# PWR_MGMT.net
KiCad netlist of a schematic drawn in Altium Designer
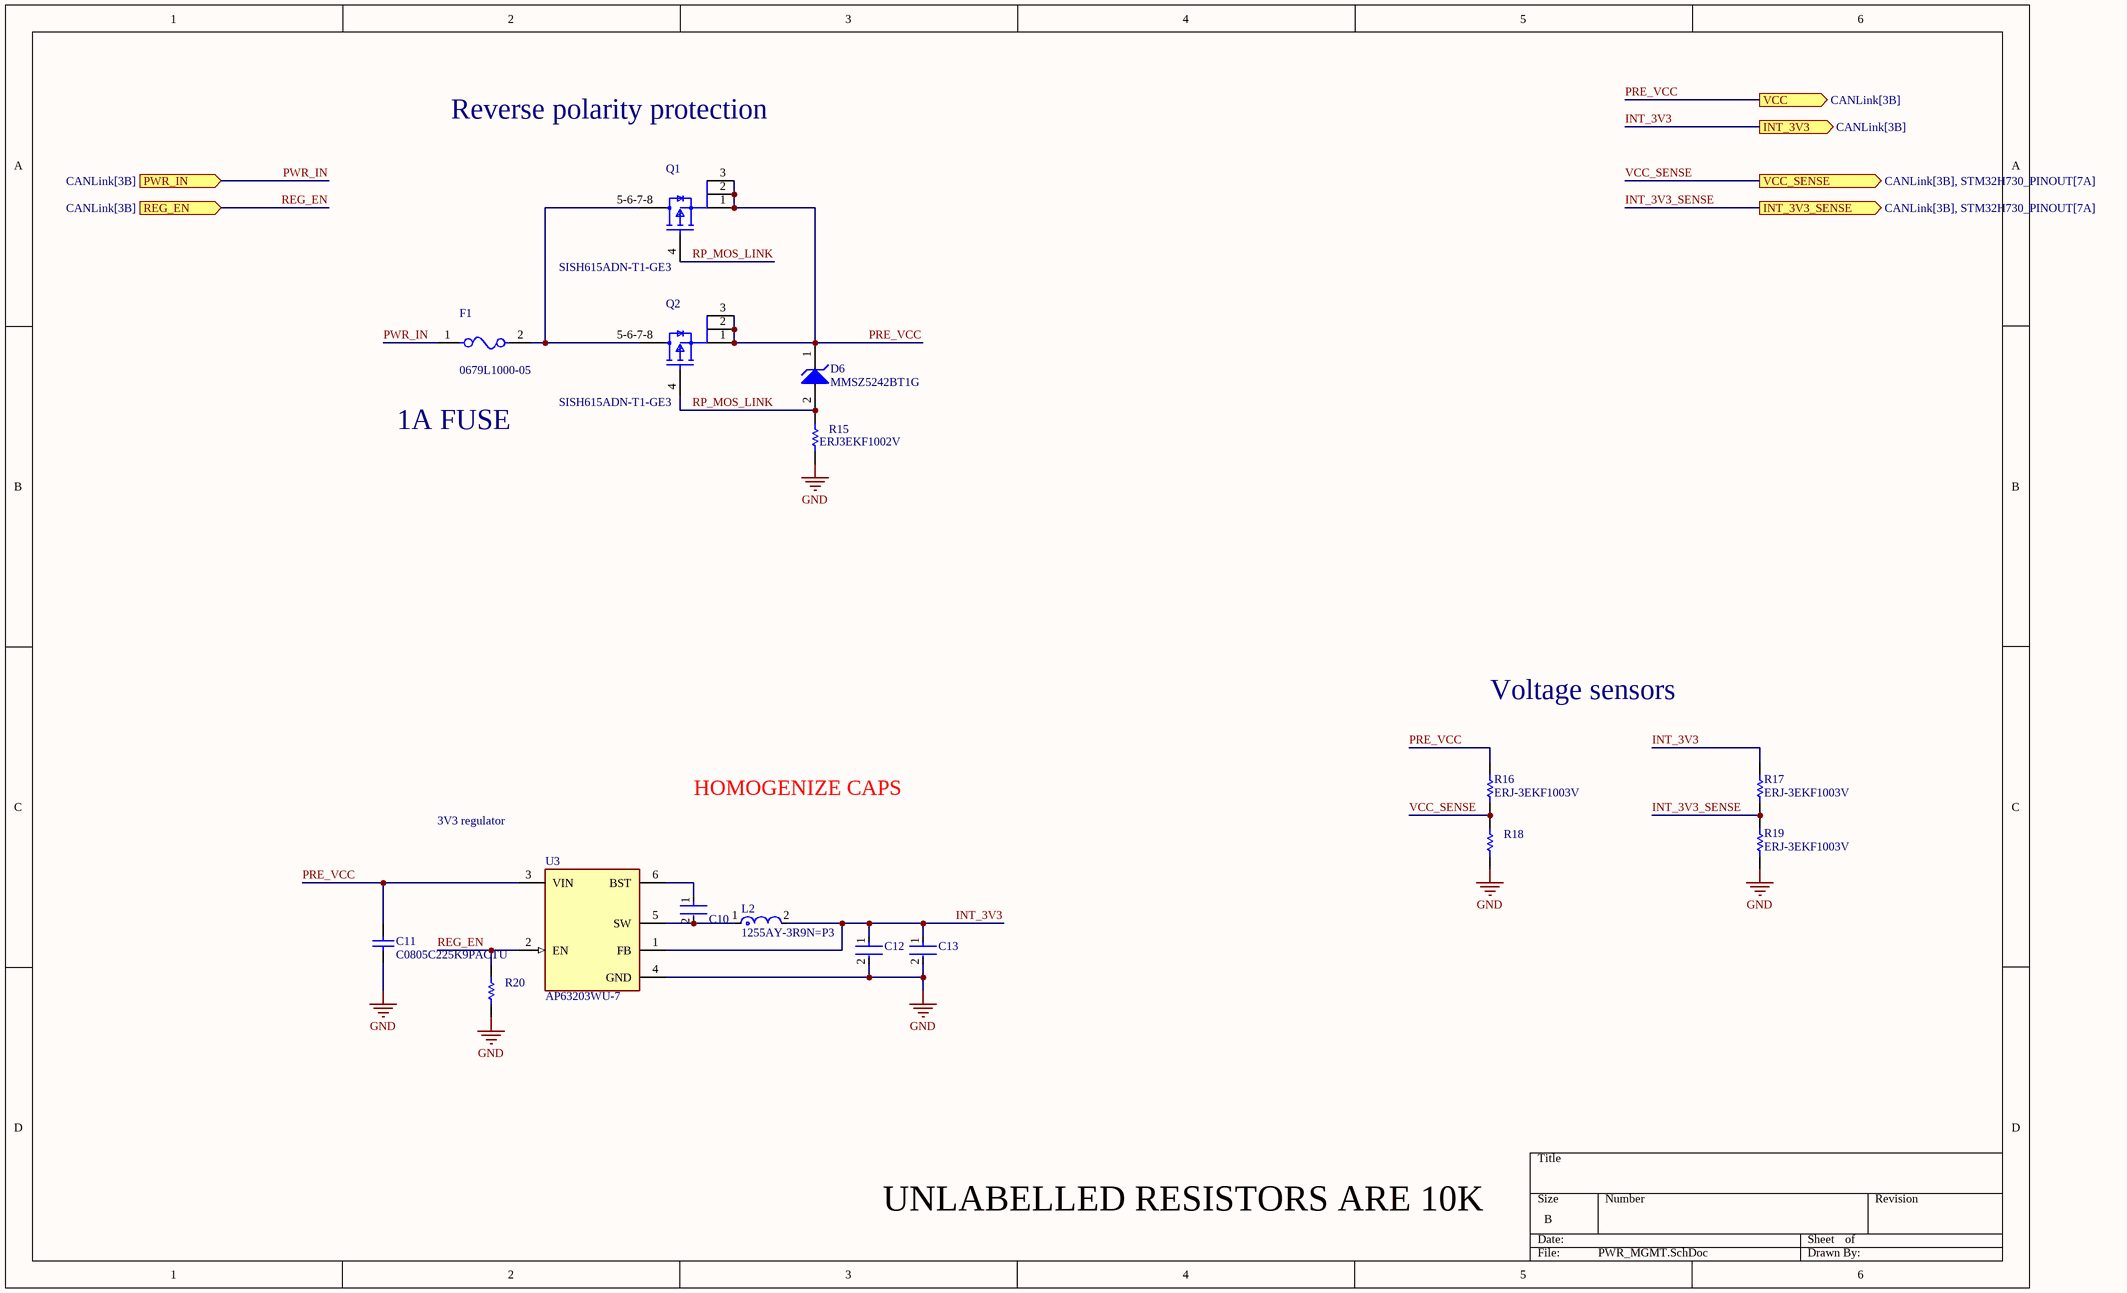
[diagram p0: PWR_MGMT.SchDoc]

(export (version "E")
  (design (tool "Eeschema 10.0.6"))
  (components
    (comp (ref "C10")
      (value "C0402C104K8PACTU")
      (footprint "FP-C0402-BB-MFG")
      (description "CAP CER 0.1UF 10V X5R 0402")
      (fields (field (name "MANUFACTURER") "Kemet") (field (name "TOLERANCE") "0.1"))
      (libsource (lib "Altium Content Vault") (part "b4654b650e69147ec39a6b967a45e02"))
    )
    (comp (ref "C11")
      (value "C0805C225K9PACTU")
      (footprint "CAPC2013X145X50ML20T25")
      (fields (field (name "MANUFACTURER") "Kemet"))
      (libsource (lib "Altium Content Vault") (part "CAP"))
    )
    (comp (ref "C12")
      (value "GRM21BR61E226ME44L")
      (footprint "FP-GRM21B-0_2-e0_2_0_7-IPC_B")
      (description "Chip Multilayer Ceramic Capacitors for General Purpose, 0805, 22uF, X5R, 15%, 20%, 25V")
      (fields (field (name "TOLERANCE") "20%") (field (name "VOLTAGE") "25V"))
      (libsource (lib "Altium Content Vault") (part "b4654b650e69147ec39a6b967a45e02"))
    )
    (comp (ref "C13")
      (value "GRM21BR61E226ME44L")
      (footprint "FP-GRM21B-0_2-e0_2_0_7-IPC_B")
      (description "Chip Multilayer Ceramic Capacitors for General Purpose, 0805, 22uF, X5R, 15%, 20%, 25V")
      (fields (field (name "TOLERANCE") "20%") (field (name "VOLTAGE") "25V"))
      (libsource (lib "Altium Content Vault") (part "b4654b650e69147ec39a6b967a45e02"))
    )
    (comp (ref "D6")
      (value "MMSZ5242BT1G")
      (footprint "ONSC-SOD-123-2-425-04_V")
      (description "Zener Voltage Regulator, 500 mW, 2-Pin SOD-123, Pb-Free, Tape and Reel")
      (fields (field (name "MANUFACTURER") "On Semiconductor"))
      (libsource (lib "Altium Content Vault") (part "ONSC-K1A2-2"))
    )
    (comp (ref "F1")
      (value "0679L1000-05")
      (footprint "FP-0679L-MFG")
      (description "DIFF P#!!!\r\n\r\nFUSE BRD MNT 1A 125VAC/VDC")
      (fields
        (field (name "OCTOPART") "https://octopart.com/0679l9150-01-bel+fuse-70850665")
        (field (name "MANUFACTURER") "Bel Fuse")
      )
      (libsource (lib "Altium Content Vault") (part "5bcf9b9f640e542cf0359d10258e979"))
    )
    (comp (ref "L2")
      (value "1255AY-3R9N=P3")
      (footprint "FP-DG6045C-MFG")
      (description "Shielded Wirewound Inductor 3.9uH 30% 4200mA 0.0264Ω SMD")
      (fields (field (name "TOLERANCE") "30%"))
      (libsource (lib "Altium Content Vault") (part "4cc4b267dca4c8e51f7102f422741d8"))
    )
    (comp (ref "Q1")
      (value "SISH615ADN-T1-GE3")
      (footprint "SISH615ADN-T1-GE3-Footprint-1")
      (description "Trans MOSFET P-CH 20V 22.1A 8-Pin PowerPAK 1212 EP T/R")
      (libsource (lib "uORocketry Hardware") (part "SISH615ADN-T1-GE3-Symbol-1"))
    )
    (comp (ref "Q2")
      (value "SISH615ADN-T1-GE3")
      (footprint "SISH615ADN-T1-GE3-Footprint-1")
      (description "Trans MOSFET P-CH 20V 22.1A 8-Pin PowerPAK 1212 EP T/R")
      (libsource (lib "uORocketry Hardware") (part "SISH615ADN-T1-GE3-Symbol-1"))
    )
    (comp (ref "R15")
      (value "ERJ3EKF1002V")
      (footprint "RESC1609X55X30LL15T15")
      (description "Chip Resistor, 10 KOhm, +/- 1%, 0.1 W, -55 to 155 degC, 0603 (1608 Metric), RoHS, Tape and Reel")
      (fields (field (name "TOLERANCE") "1%") (field (name "MANUFACTURER") "Panasonic"))
      (libsource (lib "Altium Content Vault") (part "RES-2"))
    )
    (comp (ref "R16")
      (value "ERJ-3EKF1003V")
      (footprint "RESC1608X55X30ML15T15")
      (fields (field (name "MANUFACTURER") "Panasonic"))
      (libsource (lib "Altium Content Vault") (part "RES"))
    )
    (comp (ref "R17")
      (value "ERJ-3EKF1003V")
      (footprint "RESC1608X55X30ML15T15")
      (fields (field (name "MANUFACTURER") "Panasonic"))
      (libsource (lib "Altium Content Vault") (part "RES"))
    )
    (comp (ref "R18")
      (value "ERJ3EKF1002V")
      (footprint "RESC1609X55X30LL15T15")
      (description "Chip Resistor, 10 KOhm, +/- 1%, 0.1 W, -55 to 155 degC, 0603 (1608 Metric), RoHS, Tape and Reel")
      (fields (field (name "TOLERANCE") "1%") (field (name "MANUFACTURER") "Panasonic"))
      (libsource (lib "Altium Content Vault") (part "RES-2"))
    )
    (comp (ref "R19")
      (value "ERJ-3EKF1003V")
      (footprint "RESC1608X55X30ML15T15")
      (fields (field (name "MANUFACTURER") "Panasonic"))
      (libsource (lib "Altium Content Vault") (part "RES"))
    )
    (comp (ref "R20")
      (value "ERJ3EKF1002V")
      (footprint "RESC1609X55X30LL15T15")
      (description "Chip Resistor, 10 KOhm, +/- 1%, 0.1 W, -55 to 155 degC, 0603 (1608 Metric), RoHS, Tape and Reel")
      (fields (field (name "TOLERANCE") "1%") (field (name "MANUFACTURER") "Panasonic"))
      (libsource (lib "Altium Content Vault") (part "RES-2"))
    )
    (comp (ref "U3")
      (value "AP63203WU-7")
      (footprint "FP-TSOT26-MFG")
      (description "IC REG BUCK 3.3V 2A TSOT26")
      (fields
        (field (name "MANUFACTURER") "Diodes Inc.")
        (field (name "OCTOPART") "https://octopart.com/ap63203wu-7-diodes+inc.-98099550")
      )
      (libsource (lib "Altium Content Vault") (part "0e61c2974d7114b43f01ef96ae2e524"))
    )
  )
  (nets
    (net (code "1") (name "/INT_3V3") (class "Default")
      (node (ref "C12") (pin "1") (pinfunction "1_1") (pintype "passive"))
      (node (ref "C13") (pin "1") (pinfunction "1_1") (pintype "passive"))
      (node (ref "L2") (pin "2") (pinfunction "2_2") (pintype "passive"))
      (node (ref "R17") (pin "2") (pinfunction "2_2") (pintype "passive"))
      (node (ref "U3") (pin "1") (pinfunction "FB_1") (pintype "passive"))
    )
    (net (code "2") (name "/INT_3V3_SENSE") (class "Default")
      (node (ref "R17") (pin "1") (pinfunction "1_1") (pintype "passive"))
      (node (ref "R19") (pin "2") (pinfunction "2_2") (pintype "passive"))
    )
    (net (code "3") (name "/PRE_VCC") (class "Default")
      (node (ref "C11") (pin "2") (pinfunction "2_2") (pintype "passive"))
      (node (ref "D6") (pin "1") (pinfunction "K_1") (pintype "passive"))
      (node (ref "Q1") (pin "1") (pinfunction "S_1") (pintype "passive"))
      (node (ref "Q1") (pin "2") (pinfunction "S_2") (pintype "passive"))
      (node (ref "Q1") (pin "3") (pinfunction "S_3") (pintype "passive"))
      (node (ref "Q2") (pin "1") (pinfunction "S_1") (pintype "passive"))
      (node (ref "Q2") (pin "2") (pinfunction "S_2") (pintype "passive"))
      (node (ref "Q2") (pin "3") (pinfunction "S_3") (pintype "passive"))
      (node (ref "R16") (pin "2") (pinfunction "2_2") (pintype "passive"))
      (node (ref "U3") (pin "3") (pinfunction "VIN_3") (pintype "power_in"))
    )
    (net (code "4") (name "/PWR_IN") (class "Default")
      (node (ref "F1") (pin "1") (pinfunction "1_1") (pintype "passive"))
    )
    (net (code "5") (name "/REG_EN") (class "Default")
      (node (ref "R20") (pin "1") (pinfunction "1_1") (pintype "passive"))
      (node (ref "U3") (pin "2") (pinfunction "EN_2") (pintype "input"))
    )
    (net (code "6") (name "/RP_MOS_LINK") (class "Default")
      (node (ref "D6") (pin "2") (pinfunction "A_2") (pintype "passive"))
      (node (ref "Q1") (pin "4") (pinfunction "G_4") (pintype "passive"))
      (node (ref "Q2") (pin "4") (pinfunction "G_4") (pintype "passive"))
      (node (ref "R15") (pin "1") (pinfunction "1_1") (pintype "passive"))
    )
    (net (code "7") (name "/VCC_SENSE") (class "Default")
      (node (ref "R16") (pin "1") (pinfunction "1_1") (pintype "passive"))
      (node (ref "R18") (pin "1") (pinfunction "1_1") (pintype "passive"))
    )
    (net (code "8") (name "GND") (class "Default")
      (node (ref "C11") (pin "1") (pinfunction "1_1") (pintype "passive"))
      (node (ref "C12") (pin "2") (pinfunction "2_2") (pintype "passive"))
      (node (ref "C13") (pin "2") (pinfunction "2_2") (pintype "passive"))
      (node (ref "R15") (pin "2") (pinfunction "2_2") (pintype "passive"))
      (node (ref "R18") (pin "2") (pinfunction "2_2") (pintype "passive"))
      (node (ref "R19") (pin "1") (pinfunction "1_1") (pintype "passive"))
      (node (ref "R20") (pin "2") (pinfunction "2_2") (pintype "passive"))
      (node (ref "U3") (pin "4") (pinfunction "GND_4") (pintype "power_in"))
    )
    (net (code "9") (name "Net-(Q1-D)") (class "Default")
      (node (ref "F1") (pin "2") (pinfunction "2_2") (pintype "passive"))
      (node (ref "Q1") (pin "5-6-7-8") (pinfunction "D_5-6-7-8") (pintype "passive"))
      (node (ref "Q2") (pin "5-6-7-8") (pinfunction "D_5-6-7-8") (pintype "passive"))
    )
    (net (code "10") (name "Net-(U3-BST)") (class "Default")
      (node (ref "C10") (pin "1") (pinfunction "1_1") (pintype "passive"))
      (node (ref "U3") (pin "6") (pinfunction "BST_6") (pintype "passive"))
    )
    (net (code "11") (name "Net-(U3-SW)") (class "Default")
      (node (ref "C10") (pin "2") (pinfunction "2_2") (pintype "passive"))
      (node (ref "L2") (pin "1") (pinfunction "1_1") (pintype "passive"))
      (node (ref "U3") (pin "5") (pinfunction "SW_5") (pintype "passive"))
    )
  )
)
